# stripPCB.net
KiCad netlist of a schematic drawn in EAGLE
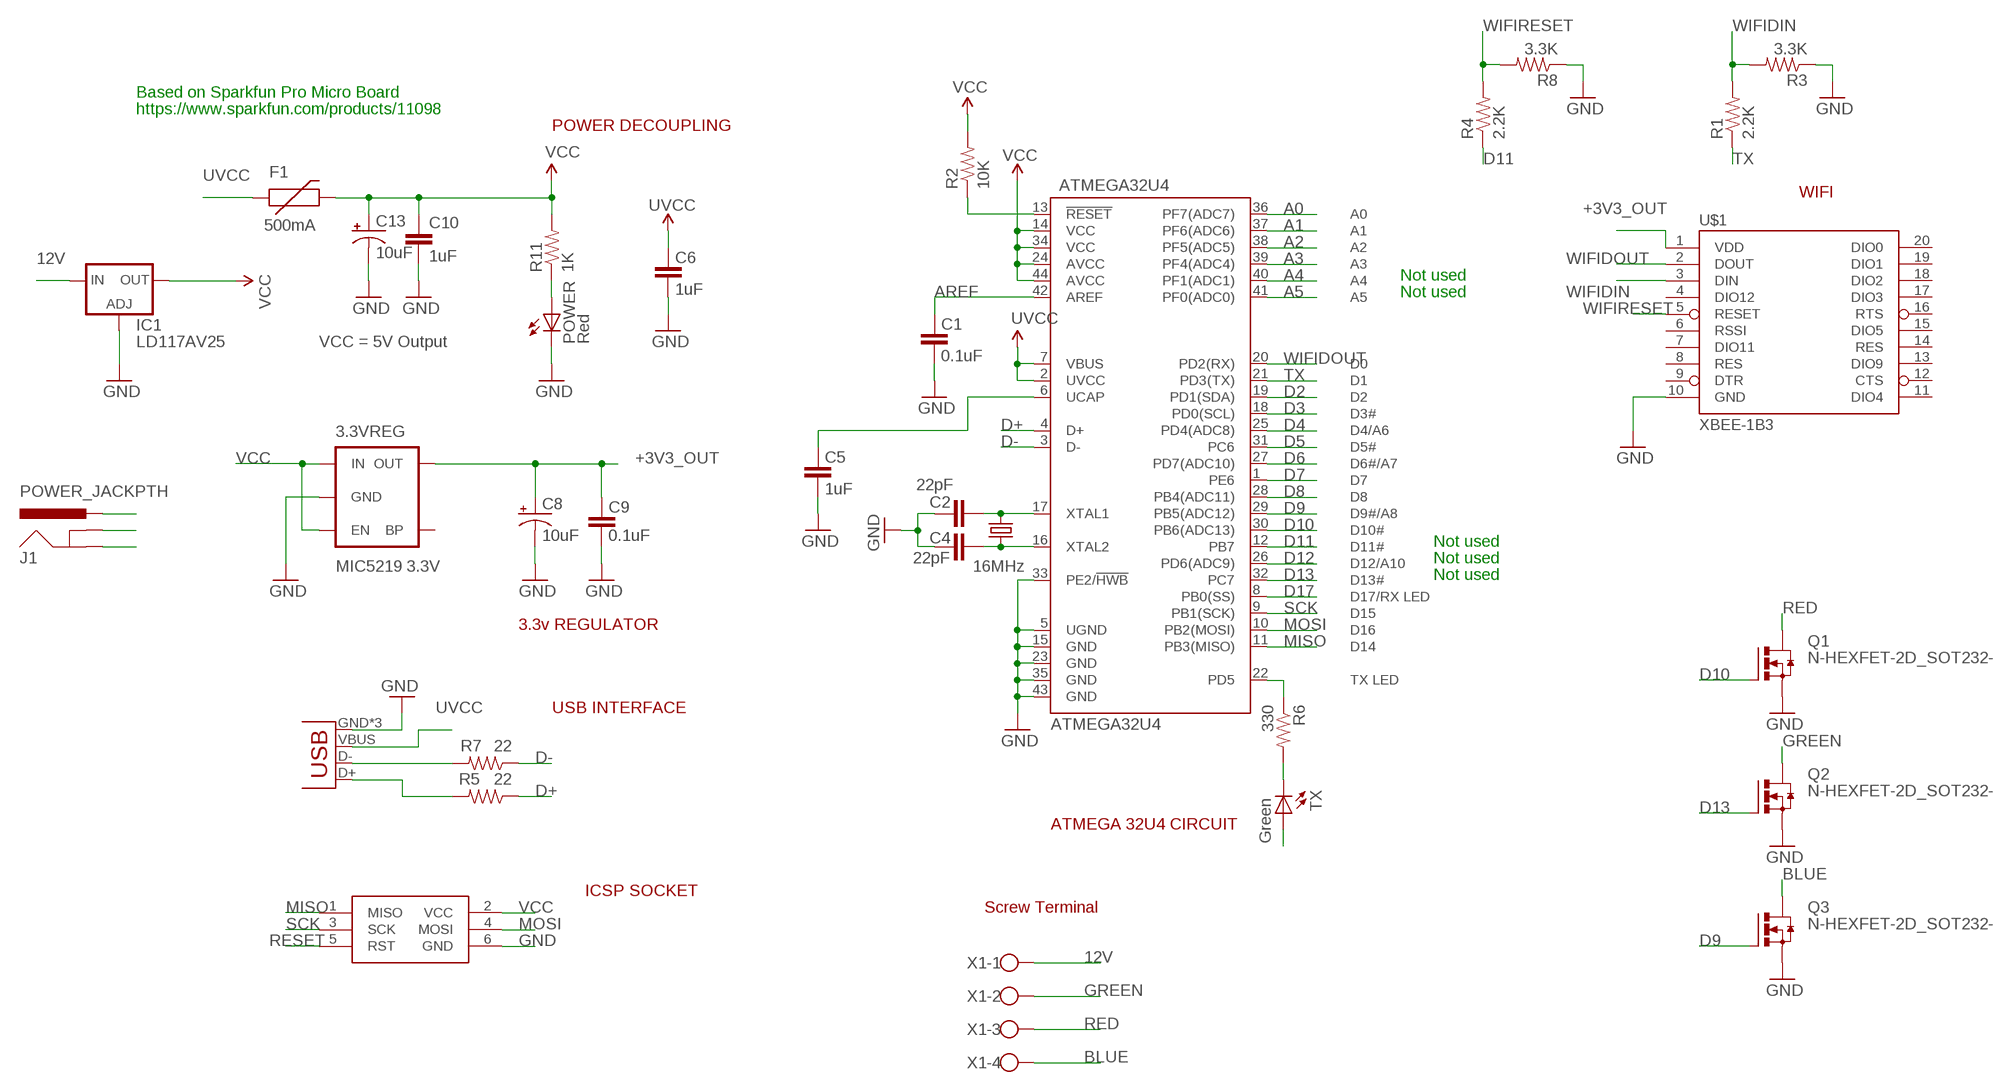
[diagram p0: schematic, sheet 1]

(export (version "E")
  (design (tool "Eeschema 10.0.6"))
  (components
    (comp (ref "3.3VREG")
      (value "MIC5219 3.3V")
      (footprint "eagle-import:SOT23-5")
      (libsource (lib "eagle-import") (part "V_REG_MIC52193.3V"))
    )
    (comp (ref "ATMEGA32U4")
      (value "ATMEGA32U4")
      (footprint "eagle-import:SPARKFUN-DIGITALIC_TQFP44")
      (libsource (lib "eagle-import") (part "ATMEGA32U4TQFP"))
    )
    (comp (ref "C1")
      (value "0.1uF")
      (footprint "eagle-import:0402-CAP")
      (libsource (lib "eagle-import") (part "CAP0402-CAP"))
    )
    (comp (ref "C2")
      (value "22pF")
      (footprint "eagle-import:0402-CAP")
      (libsource (lib "eagle-import") (part "CAP0402-CAP"))
    )
    (comp (ref "C4")
      (value "22pF")
      (footprint "eagle-import:0402-CAP")
      (libsource (lib "eagle-import") (part "CAP0402-CAP"))
    )
    (comp (ref "C5")
      (value "1uF")
      (footprint "eagle-import:0402-CAP")
      (libsource (lib "eagle-import") (part "CAP0402-CAP"))
    )
    (comp (ref "C6")
      (value "1uF")
      (footprint "eagle-import:0402-CAP")
      (libsource (lib "eagle-import") (part "CAP0402-CAP"))
    )
    (comp (ref "C8")
      (value "10uF")
      (footprint "eagle-import:EIA3216")
      (libsource (lib "eagle-import") (part "CAP_POL1206"))
    )
    (comp (ref "C9")
      (value "0.1uF")
      (footprint "eagle-import:0402-CAP")
      (libsource (lib "eagle-import") (part "CAP0402-CAP"))
    )
    (comp (ref "C10")
      (value "1uF")
      (footprint "eagle-import:0402-CAP")
      (libsource (lib "eagle-import") (part "CAP0402-CAP"))
    )
    (comp (ref "C13")
      (value "10uF")
      (footprint "eagle-import:EIA3216")
      (libsource (lib "eagle-import") (part "CAP_POL1206"))
    )
    (comp (ref "F1")
      (value "500mA")
      (footprint "eagle-import:PTC-1206")
      (libsource (lib "eagle-import") (part "PTCSMD"))
    )
    (comp (ref "IC1")
      (value "LD117AV25")
      (footprint "eagle-import:TO220L1")
      (libsource (lib "eagle-import") (part "LD117A?V25"))
    )
    (comp (ref "ISP1")
      (value "AVRISP-6")
      (footprint "eagle-import:AVRISP")
      (libsource (lib "eagle-import") (part "AVRISP-6"))
    )
    (comp (ref "J1")
      (value "POWER_JACKPTH")
      (footprint "eagle-import:POWER_JACK_PTH")
      (libsource (lib "eagle-import") (part "POWER_JACKPTH"))
    )
    (comp (ref "POWER")
      (value "Red")
      (footprint "eagle-import:LED-0603")
      (libsource (lib "eagle-import") (part "LED0603"))
    )
    (comp (ref "Q1")
      (value "N-HEXFET-2D_SOT232-")
      (footprint "eagle-import:SOT223")
      (libsource (lib "eagle-import") (part "N-HEXFET-2D_?-SOT232"))
    )
    (comp (ref "Q2")
      (value "N-HEXFET-2D_SOT232-")
      (footprint "eagle-import:SOT223")
      (libsource (lib "eagle-import") (part "N-HEXFET-2D_?-SOT232"))
    )
    (comp (ref "Q3")
      (value "N-HEXFET-2D_SOT232-")
      (footprint "eagle-import:SOT223")
      (libsource (lib "eagle-import") (part "N-HEXFET-2D_?-SOT232"))
    )
    (comp (ref "R1")
      (value "2.2K")
      (footprint "eagle-import:0402-RES")
      (libsource (lib "eagle-import") (part "RESISTOR0402-RES"))
    )
    (comp (ref "R2")
      (value "10K")
      (footprint "eagle-import:0402-RES")
      (libsource (lib "eagle-import") (part "RESISTOR0402-RES"))
    )
    (comp (ref "R3")
      (value "3.3K")
      (footprint "eagle-import:0402-RES")
      (libsource (lib "eagle-import") (part "RESISTOR0402-RES"))
    )
    (comp (ref "R4")
      (value "2.2K")
      (footprint "eagle-import:0402-RES")
      (libsource (lib "eagle-import") (part "RESISTOR0402-RES"))
    )
    (comp (ref "R5")
      (value "22")
      (footprint "eagle-import:0402-RES")
      (libsource (lib "eagle-import") (part "RESISTOR0402-RES"))
    )
    (comp (ref "R6")
      (value "330")
      (footprint "eagle-import:0402-RES")
      (libsource (lib "eagle-import") (part "RESISTOR0402-RES"))
    )
    (comp (ref "R7")
      (value "22")
      (footprint "eagle-import:0402-RES")
      (libsource (lib "eagle-import") (part "RESISTOR0402-RES"))
    )
    (comp (ref "R8")
      (value "3.3K")
      (footprint "eagle-import:0402-RES")
      (libsource (lib "eagle-import") (part "RESISTOR0402-RES"))
    )
    (comp (ref "R11")
      (value "1K")
      (footprint "eagle-import:0402-RES")
      (libsource (lib "eagle-import") (part "RESISTOR0402-RES"))
    )
    (comp (ref "TX")
      (value "Green")
      (footprint "eagle-import:LED-0603")
      (libsource (lib "eagle-import") (part "LED0603"))
    )
    (comp (ref "U$1")
      (value "XBEE-1B3")
      (footprint "eagle-import:XBEE-SMD")
      (libsource (lib "eagle-import") (part "XBEE-1B3"))
    )
    (comp (ref "X1")
      (value "W237-4")
      (footprint "eagle-import:W237-4")
      (libsource (lib "eagle-import") (part "W237-4"))
    )
    (comp (ref "X2")
      (value "USB-MICROB")
      (footprint "eagle-import:USB-MICROB")
      (libsource (lib "eagle-import") (part "USB-MICROB"))
    )
    (comp (ref "Y1")
      (value "16MHz")
      (footprint "eagle-import:CRYSTAL-SMD-5X3")
      (libsource (lib "eagle-import") (part "CRYSTAL5X3"))
    )
  )
  (nets
    (net (code "1") (name "/+3V3_OUT") (class "Default")
      (node (ref "3.3VREG") (pin "5") (pinfunction "OUT_5") (pintype "passive"))
      (node (ref "C8") (pin "A") (pinfunction "+_A") (pintype "passive"))
      (node (ref "C9") (pin "2") (pinfunction "2_2") (pintype "passive"))
      (node (ref "U$1") (pin "1") (pinfunction "VDD_1") (pintype "power_in"))
    )
    (net (code "2") (name "/12V") (class "Default")
      (node (ref "IC1") (pin "3") (pinfunction "IN_3") (pintype "input"))
      (node (ref "J1") (pin "PWR") (pinfunction "PWR_PWR") (pintype "bidirectional"))
      (node (ref "X1") (pin "1") (pinfunction "KL_1") (pintype "passive"))
    )
    (net (code "3") (name "/A0") (class "Default")
      (node (ref "ATMEGA32U4") (pin "36") (pinfunction "PF7(ADC7)_36") (pintype "bidirectional"))
    )
    (net (code "4") (name "/A1") (class "Default")
      (node (ref "ATMEGA32U4") (pin "37") (pinfunction "PF6(ADC6)_37") (pintype "bidirectional"))
    )
    (net (code "5") (name "/A2") (class "Default")
      (node (ref "ATMEGA32U4") (pin "38") (pinfunction "PF5(ADC5)_38") (pintype "bidirectional"))
    )
    (net (code "6") (name "/A3") (class "Default")
      (node (ref "ATMEGA32U4") (pin "39") (pinfunction "PF4(ADC4)_39") (pintype "bidirectional"))
    )
    (net (code "7") (name "/A4") (class "Default")
      (node (ref "ATMEGA32U4") (pin "40") (pinfunction "PF1(ADC1)_40") (pintype "bidirectional"))
    )
    (net (code "8") (name "/A5") (class "Default")
      (node (ref "ATMEGA32U4") (pin "41") (pinfunction "PF0(ADC0)_41") (pintype "bidirectional"))
    )
    (net (code "9") (name "/AREF") (class "Default")
      (node (ref "ATMEGA32U4") (pin "42") (pinfunction "AREF_42") (pintype "bidirectional"))
      (node (ref "C1") (pin "2") (pinfunction "2_2") (pintype "passive"))
    )
    (net (code "10") (name "/BLUE") (class "Default")
      (node (ref "Q3") (pin "2") (pinfunction "D_2") (pintype "passive"))
      (node (ref "Q3") (pin "4") (pinfunction "D_4") (pintype "passive"))
      (node (ref "X1") (pin "4") (pinfunction "KL_4") (pintype "passive"))
    )
    (net (code "11") (name "/D+") (class "Default")
      (node (ref "ATMEGA32U4") (pin "4") (pinfunction "D+_4") (pintype "bidirectional"))
      (node (ref "R5") (pin "1") (pinfunction "1_1") (pintype "passive"))
    )
    (net (code "12") (name "/D-") (class "Default")
      (node (ref "ATMEGA32U4") (pin "3") (pinfunction "D-_3") (pintype "bidirectional"))
      (node (ref "R7") (pin "1") (pinfunction "1_1") (pintype "passive"))
    )
    (net (code "13") (name "/D2") (class "Default")
      (node (ref "ATMEGA32U4") (pin "19") (pinfunction "PD1(SDA)_19") (pintype "bidirectional"))
    )
    (net (code "14") (name "/D3") (class "Default")
      (node (ref "ATMEGA32U4") (pin "18") (pinfunction "PD0(SCL)_18") (pintype "bidirectional"))
    )
    (net (code "15") (name "/D4") (class "Default")
      (node (ref "ATMEGA32U4") (pin "25") (pinfunction "PD4(ADC8)_25") (pintype "bidirectional"))
    )
    (net (code "16") (name "/D5") (class "Default")
      (node (ref "ATMEGA32U4") (pin "31") (pinfunction "PC6_31") (pintype "bidirectional"))
    )
    (net (code "17") (name "/D6") (class "Default")
      (node (ref "ATMEGA32U4") (pin "27") (pinfunction "PD7(ADC10)_27") (pintype "bidirectional"))
    )
    (net (code "18") (name "/D7") (class "Default")
      (node (ref "ATMEGA32U4") (pin "1") (pinfunction "PE6_1") (pintype "bidirectional"))
    )
    (net (code "19") (name "/D8") (class "Default")
      (node (ref "ATMEGA32U4") (pin "28") (pinfunction "PB4(ADC11)_28") (pintype "bidirectional"))
    )
    (net (code "20") (name "/D9") (class "Default")
      (node (ref "ATMEGA32U4") (pin "29") (pinfunction "PB5(ADC12)_29") (pintype "bidirectional"))
      (node (ref "Q3") (pin "1") (pinfunction "G_1") (pintype "passive"))
    )
    (net (code "21") (name "/D10") (class "Default")
      (node (ref "ATMEGA32U4") (pin "30") (pinfunction "PB6(ADC13)_30") (pintype "bidirectional"))
      (node (ref "Q1") (pin "1") (pinfunction "G_1") (pintype "passive"))
    )
    (net (code "22") (name "/D11") (class "Default")
      (node (ref "ATMEGA32U4") (pin "12") (pinfunction "PB7_12") (pintype "bidirectional"))
      (node (ref "R4") (pin "1") (pinfunction "1_1") (pintype "passive"))
    )
    (net (code "23") (name "/D12") (class "Default")
      (node (ref "ATMEGA32U4") (pin "26") (pinfunction "PD6(ADC9)_26") (pintype "bidirectional"))
    )
    (net (code "24") (name "/D13") (class "Default")
      (node (ref "ATMEGA32U4") (pin "32") (pinfunction "PC7_32") (pintype "bidirectional"))
      (node (ref "Q2") (pin "1") (pinfunction "G_1") (pintype "passive"))
    )
    (net (code "25") (name "/D17") (class "Default")
      (node (ref "ATMEGA32U4") (pin "8") (pinfunction "PB0(SS)_8") (pintype "bidirectional"))
    )
    (net (code "26") (name "/GREEN") (class "Default")
      (node (ref "Q2") (pin "2") (pinfunction "D_2") (pintype "passive"))
      (node (ref "Q2") (pin "4") (pinfunction "D_4") (pintype "passive"))
      (node (ref "X1") (pin "2") (pinfunction "KL_2") (pintype "passive"))
    )
    (net (code "27") (name "/MISO") (class "Default")
      (node (ref "ATMEGA32U4") (pin "11") (pinfunction "PB3(MISO)_11") (pintype "bidirectional"))
      (node (ref "ISP1") (pin "1") (pinfunction "MISO_1") (pintype "input"))
    )
    (net (code "28") (name "/MOSI") (class "Default")
      (node (ref "ATMEGA32U4") (pin "10") (pinfunction "PB2(MOSI)_10") (pintype "bidirectional"))
      (node (ref "ISP1") (pin "4") (pinfunction "MOSI_4") (pintype "output"))
    )
    (net (code "29") (name "/RED") (class "Default")
      (node (ref "Q1") (pin "2") (pinfunction "D_2") (pintype "passive"))
      (node (ref "Q1") (pin "4") (pinfunction "D_4") (pintype "passive"))
      (node (ref "X1") (pin "3") (pinfunction "KL_3") (pintype "passive"))
    )
    (net (code "30") (name "/RESET") (class "Default")
      (node (ref "ATMEGA32U4") (pin "13") (pinfunction "~{RESET}_13") (pintype "bidirectional"))
      (node (ref "ISP1") (pin "5") (pinfunction "RST_5") (pintype "output"))
      (node (ref "R2") (pin "1") (pinfunction "1_1") (pintype "passive"))
    )
    (net (code "31") (name "/SCK") (class "Default")
      (node (ref "ATMEGA32U4") (pin "9") (pinfunction "PB1(SCK)_9") (pintype "bidirectional"))
      (node (ref "ISP1") (pin "3") (pinfunction "SCK_3") (pintype "output"))
    )
    (net (code "32") (name "/TX") (class "Default")
      (node (ref "ATMEGA32U4") (pin "21") (pinfunction "PD3(TX)_21") (pintype "bidirectional"))
      (node (ref "R1") (pin "1") (pinfunction "1_1") (pintype "passive"))
    )
    (net (code "33") (name "/WIFIDIN") (class "Default")
      (node (ref "R1") (pin "2") (pinfunction "2_2") (pintype "passive"))
      (node (ref "R3") (pin "2") (pinfunction "2_2") (pintype "passive"))
      (node (ref "U$1") (pin "3") (pinfunction "DIN_3") (pintype "input"))
    )
    (net (code "34") (name "/WIFIDOUT") (class "Default")
      (node (ref "ATMEGA32U4") (pin "20") (pinfunction "PD2(RX)_20") (pintype "bidirectional"))
      (node (ref "U$1") (pin "2") (pinfunction "DOUT_2") (pintype "output"))
    )
    (net (code "35") (name "/WIFIRESET") (class "Default")
      (node (ref "R4") (pin "2") (pinfunction "2_2") (pintype "passive"))
      (node (ref "R8") (pin "2") (pinfunction "2_2") (pintype "passive"))
      (node (ref "U$1") (pin "5") (pinfunction "RESET_5") (pintype "input"))
    )
    (net (code "36") (name "GND") (class "Default")
      (node (ref "3.3VREG") (pin "2") (pinfunction "GND_2") (pintype "input"))
      (node (ref "ATMEGA32U4") (pin "15") (pinfunction "GND_15") (pintype "bidirectional"))
      (node (ref "ATMEGA32U4") (pin "23") (pinfunction "GND_23") (pintype "bidirectional"))
      (node (ref "ATMEGA32U4") (pin "33") (pinfunction "PE2/~{HWB}_33") (pintype "bidirectional"))
      (node (ref "ATMEGA32U4") (pin "35") (pinfunction "GND_35") (pintype "bidirectional"))
      (node (ref "ATMEGA32U4") (pin "43") (pinfunction "GND_43") (pintype "bidirectional"))
      (node (ref "ATMEGA32U4") (pin "5") (pinfunction "UGND_5") (pintype "bidirectional"))
      (node (ref "C1") (pin "1") (pinfunction "1_1") (pintype "passive"))
      (node (ref "C10") (pin "2") (pinfunction "2_2") (pintype "passive"))
      (node (ref "C13") (pin "C") (pinfunction "-_C") (pintype "passive"))
      (node (ref "C2") (pin "2") (pinfunction "2_2") (pintype "passive"))
      (node (ref "C4") (pin "2") (pinfunction "2_2") (pintype "passive"))
      (node (ref "C5") (pin "1") (pinfunction "1_1") (pintype "passive"))
      (node (ref "C6") (pin "1") (pinfunction "1_1") (pintype "passive"))
      (node (ref "C8") (pin "C") (pinfunction "-_C") (pintype "passive"))
      (node (ref "C9") (pin "1") (pinfunction "1_1") (pintype "passive"))
      (node (ref "IC1") (pin "1") (pinfunction "ADJ_1") (pintype "input"))
      (node (ref "ISP1") (pin "6") (pinfunction "GND_6") (pintype "power_in"))
      (node (ref "J1") (pin "GND") (pinfunction "GND_GND") (pintype "bidirectional"))
      (node (ref "J1") (pin "GNDBREAK") (pinfunction "GNDBREAK_GNDBREAK") (pintype "bidirectional"))
      (node (ref "POWER") (pin "C") (pinfunction "C_C") (pintype "passive"))
      (node (ref "Q1") (pin "3") (pinfunction "S_3") (pintype "passive"))
      (node (ref "Q2") (pin "3") (pinfunction "S_3") (pintype "passive"))
      (node (ref "Q3") (pin "3") (pinfunction "S_3") (pintype "passive"))
      (node (ref "R3") (pin "1") (pinfunction "1_1") (pintype "passive"))
      (node (ref "R8") (pin "1") (pinfunction "1_1") (pintype "passive"))
      (node (ref "U$1") (pin "10") (pinfunction "GND_10") (pintype "power_in"))
      (node (ref "X2") (pin "GND") (pinfunction "GND_GND") (pintype "bidirectional"))
      (node (ref "X2") (pin "MT1") (pinfunction "GND_MT1") (pintype "bidirectional"))
      (node (ref "X2") (pin "MT2") (pinfunction "GND_MT2") (pintype "bidirectional"))
    )
    (net (code "37") (name "Net-(ATMEGA32U4-PD5)") (class "Default")
      (node (ref "ATMEGA32U4") (pin "22") (pinfunction "PD5_22") (pintype "bidirectional"))
      (node (ref "R6") (pin "1") (pinfunction "1_1") (pintype "passive"))
    )
    (net (code "38") (name "Net-(ATMEGA32U4-UCAP)") (class "Default")
      (node (ref "ATMEGA32U4") (pin "6") (pinfunction "UCAP_6") (pintype "bidirectional"))
      (node (ref "C5") (pin "2") (pinfunction "2_2") (pintype "passive"))
    )
    (net (code "39") (name "Net-(ATMEGA32U4-XTAL1)") (class "Default")
      (node (ref "ATMEGA32U4") (pin "17") (pinfunction "XTAL1_17") (pintype "bidirectional"))
      (node (ref "C2") (pin "1") (pinfunction "1_1") (pintype "passive"))
      (node (ref "Y1") (pin "3") (pinfunction "2_3") (pintype "passive"))
    )
    (net (code "40") (name "Net-(ATMEGA32U4-XTAL2)") (class "Default")
      (node (ref "ATMEGA32U4") (pin "16") (pinfunction "XTAL2_16") (pintype "bidirectional"))
      (node (ref "C4") (pin "1") (pinfunction "1_1") (pintype "passive"))
      (node (ref "Y1") (pin "1") (pinfunction "1_1") (pintype "passive"))
    )
    (net (code "41") (name "Net-(POWER-PadA)") (class "Default")
      (node (ref "POWER") (pin "A") (pinfunction "A_A") (pintype "passive"))
      (node (ref "R11") (pin "1") (pinfunction "1_1") (pintype "passive"))
    )
    (net (code "42") (name "Net-(R5-Pad2)") (class "Default")
      (node (ref "R5") (pin "2") (pinfunction "2_2") (pintype "passive"))
      (node (ref "X2") (pin "D+") (pinfunction "D+_D+") (pintype "bidirectional"))
    )
    (net (code "43") (name "Net-(R6-Pad2)") (class "Default")
      (node (ref "R6") (pin "2") (pinfunction "2_2") (pintype "passive"))
      (node (ref "TX") (pin "C") (pinfunction "C_C") (pintype "passive"))
    )
    (net (code "44") (name "Net-(R7-Pad2)") (class "Default")
      (node (ref "R7") (pin "2") (pinfunction "2_2") (pintype "passive"))
      (node (ref "X2") (pin "D-") (pinfunction "D-_D-") (pintype "bidirectional"))
    )
    (net (code "45") (name "UVCC") (class "Default")
      (node (ref "ATMEGA32U4") (pin "2") (pinfunction "UVCC_2") (pintype "bidirectional"))
      (node (ref "ATMEGA32U4") (pin "7") (pinfunction "VBUS_7") (pintype "bidirectional"))
      (node (ref "C6") (pin "2") (pinfunction "2_2") (pintype "passive"))
      (node (ref "F1") (pin "1") (pinfunction "1_1") (pintype "bidirectional"))
      (node (ref "X2") (pin "VBUS") (pinfunction "VBUS_VBUS") (pintype "bidirectional"))
    )
    (net (code "46") (name "VCC") (class "Default")
      (node (ref "3.3VREG") (pin "1") (pinfunction "IN_1") (pintype "input"))
      (node (ref "3.3VREG") (pin "3") (pinfunction "EN_3") (pintype "input"))
      (node (ref "ATMEGA32U4") (pin "14") (pinfunction "VCC_14") (pintype "bidirectional"))
      (node (ref "ATMEGA32U4") (pin "24") (pinfunction "AVCC_24") (pintype "bidirectional"))
      (node (ref "ATMEGA32U4") (pin "34") (pinfunction "VCC_34") (pintype "bidirectional"))
      (node (ref "ATMEGA32U4") (pin "44") (pinfunction "AVCC_44") (pintype "bidirectional"))
      (node (ref "C10") (pin "1") (pinfunction "1_1") (pintype "passive"))
      (node (ref "C13") (pin "A") (pinfunction "+_A") (pintype "passive"))
      (node (ref "F1") (pin "2") (pinfunction "2_2") (pintype "bidirectional"))
      (node (ref "IC1") (pin "2") (pinfunction "OUT_2") (pintype "passive"))
      (node (ref "ISP1") (pin "2") (pinfunction "VCC_2") (pintype "power_in"))
      (node (ref "R11") (pin "2") (pinfunction "2_2") (pintype "passive"))
      (node (ref "R2") (pin "2") (pinfunction "2_2") (pintype "passive"))
      (node (ref "TX") (pin "A") (pinfunction "A_A") (pintype "passive"))
    )
    (net (code "47") (name "unconnected-(3.3VREG-BP-Pad4)") (class "Default")
      (node (ref "3.3VREG") (pin "4") (pinfunction "BP_4") (pintype "input"))
    )
    (net (code "48") (name "unconnected-(U$1-CTS-Pad12)") (class "Default")
      (node (ref "U$1") (pin "12") (pinfunction "CTS_12") (pintype "output"))
    )
    (net (code "49") (name "unconnected-(U$1-DIO0-Pad20)") (class "Default")
      (node (ref "U$1") (pin "20") (pinfunction "DIO0_20") (pintype "bidirectional"))
    )
    (net (code "50") (name "unconnected-(U$1-DIO1-Pad19)") (class "Default")
      (node (ref "U$1") (pin "19") (pinfunction "DIO1_19") (pintype "bidirectional"))
    )
    (net (code "51") (name "unconnected-(U$1-DIO2-Pad18)") (class "Default")
      (node (ref "U$1") (pin "18") (pinfunction "DIO2_18") (pintype "bidirectional"))
    )
    (net (code "52") (name "unconnected-(U$1-DIO3-Pad17)") (class "Default")
      (node (ref "U$1") (pin "17") (pinfunction "DIO3_17") (pintype "bidirectional"))
    )
    (net (code "53") (name "unconnected-(U$1-DIO4-Pad11)") (class "Default")
      (node (ref "U$1") (pin "11") (pinfunction "DIO4_11") (pintype "bidirectional"))
    )
    (net (code "54") (name "unconnected-(U$1-DIO5-Pad15)") (class "Default")
      (node (ref "U$1") (pin "15") (pinfunction "DIO5_15") (pintype "bidirectional"))
    )
    (net (code "55") (name "unconnected-(U$1-DIO9-Pad13)") (class "Default")
      (node (ref "U$1") (pin "13") (pinfunction "DIO9_13") (pintype "bidirectional"))
    )
    (net (code "56") (name "unconnected-(U$1-DIO11-Pad7)") (class "Default")
      (node (ref "U$1") (pin "7") (pinfunction "DIO11_7") (pintype "bidirectional"))
    )
    (net (code "57") (name "unconnected-(U$1-DIO12-Pad4)") (class "Default")
      (node (ref "U$1") (pin "4") (pinfunction "DIO12_4") (pintype "bidirectional"))
    )
    (net (code "58") (name "unconnected-(U$1-DTR-Pad9)") (class "Default")
      (node (ref "U$1") (pin "9") (pinfunction "DTR_9") (pintype "bidirectional"))
    )
    (net (code "59") (name "unconnected-(U$1-RES-Pad8)") (class "Default")
      (node (ref "U$1") (pin "8") (pinfunction "RES_8") (pintype "bidirectional"))
    )
    (net (code "60") (name "unconnected-(U$1-RES-Pad14)") (class "Default")
      (node (ref "U$1") (pin "14") (pinfunction "RES_14") (pintype "bidirectional"))
    )
    (net (code "61") (name "unconnected-(U$1-RSSI-Pad6)") (class "Default")
      (node (ref "U$1") (pin "6") (pinfunction "RSSI_6") (pintype "bidirectional"))
    )
    (net (code "62") (name "unconnected-(U$1-RTS-Pad16)") (class "Default")
      (node (ref "U$1") (pin "16") (pinfunction "RTS_16") (pintype "input"))
    )
  )
)
